# SDRAM_1.net
KiCad netlist of a schematic drawn in Altium Designer
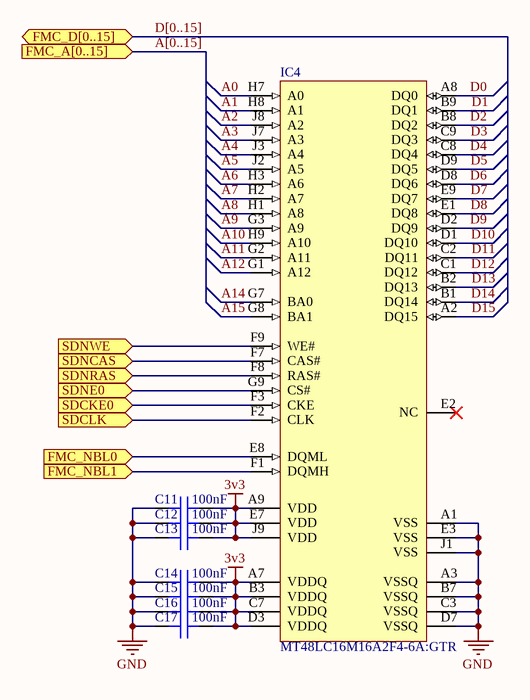
[diagram p0: SDRAM 1.SchDoc]

(export (version "E")
  (design (tool "Eeschema 10.0.6"))
  (components
    (comp (ref "C11")
      (value "100nF")
      (footprint "CAP 0603/1608")
      (description "Ceramic, SMT Capacitor")
      (fields
        (field (name "MANUFACTURER") "Samsung")
        (field (name "MANUFACTURER PART NUMBER") "CL10B104JB8NNNC")
      )
      (libsource (lib "yildizIoT Library") (part "Capacitor - Ceramic"))
    )
    (comp (ref "C12")
      (value "100nF")
      (footprint "CAP 0603/1608")
      (description "Ceramic, SMT Capacitor")
      (fields
        (field (name "MANUFACTURER") "Samsung")
        (field (name "MANUFACTURER PART NUMBER") "CL10B104JB8NNNC")
      )
      (libsource (lib "yildizIoT Library") (part "Capacitor - Ceramic"))
    )
    (comp (ref "C13")
      (value "100nF")
      (footprint "CAP 0603/1608")
      (description "Ceramic, SMT Capacitor")
      (fields
        (field (name "MANUFACTURER") "Samsung")
        (field (name "MANUFACTURER PART NUMBER") "CL10B104JB8NNNC")
      )
      (libsource (lib "yildizIoT Library") (part "Capacitor - Ceramic"))
    )
    (comp (ref "C14")
      (value "100nF")
      (footprint "CAP 0603/1608")
      (description "Ceramic, SMT Capacitor")
      (fields
        (field (name "MANUFACTURER") "Samsung")
        (field (name "MANUFACTURER PART NUMBER") "CL10B104JB8NNNC")
      )
      (libsource (lib "yildizIoT Library") (part "Capacitor - Ceramic"))
    )
    (comp (ref "C15")
      (value "100nF")
      (footprint "CAP 0603/1608")
      (description "Ceramic, SMT Capacitor")
      (fields
        (field (name "MANUFACTURER") "Samsung")
        (field (name "MANUFACTURER PART NUMBER") "CL10B104JB8NNNC")
      )
      (libsource (lib "yildizIoT Library") (part "Capacitor - Ceramic"))
    )
    (comp (ref "C16")
      (value "100nF")
      (footprint "CAP 0603/1608")
      (description "Ceramic, SMT Capacitor")
      (fields
        (field (name "MANUFACTURER") "Samsung")
        (field (name "MANUFACTURER PART NUMBER") "CL10B104JB8NNNC")
      )
      (libsource (lib "yildizIoT Library") (part "Capacitor - Ceramic"))
    )
    (comp (ref "C17")
      (value "100nF")
      (footprint "CAP 0603/1608")
      (description "Ceramic, SMT Capacitor")
      (fields
        (field (name "MANUFACTURER") "Samsung")
        (field (name "MANUFACTURER PART NUMBER") "CL10B104JB8NNNC")
      )
      (libsource (lib "yildizIoT Library") (part "Capacitor - Ceramic"))
    )
    (comp (ref "IC4")
      (value "MT48LC16M16A2F4-6A:GTR")
      (footprint "MICRON VFBGA-54 8X14MM")
      (fields (field (name "MANUFACTURER") "Alliance Memory"))
      (libsource (lib "yildizIoT Library") (part "MICRON 256Mb SDRAM"))
    )
  )
  (nets
    (net (code "2") (name "/A0") (class "Default")
      (node (ref "IC4") (pin "H7") (pinfunction "A0_H7") (pintype "input"))
    )
    (net (code "3") (name "/A1") (class "Default")
      (node (ref "IC4") (pin "H8") (pinfunction "A1_H8") (pintype "input"))
    )
    (net (code "4") (name "/A2") (class "Default")
      (node (ref "IC4") (pin "J8") (pinfunction "A2_J8") (pintype "input"))
    )
    (net (code "5") (name "/A3") (class "Default")
      (node (ref "IC4") (pin "J7") (pinfunction "A3_J7") (pintype "input"))
    )
    (net (code "6") (name "/A4") (class "Default")
      (node (ref "IC4") (pin "J3") (pinfunction "A4_J3") (pintype "input"))
    )
    (net (code "7") (name "/A5") (class "Default")
      (node (ref "IC4") (pin "J2") (pinfunction "A5_J2") (pintype "input"))
    )
    (net (code "8") (name "/A6") (class "Default")
      (node (ref "IC4") (pin "H3") (pinfunction "A6_H3") (pintype "input"))
    )
    (net (code "9") (name "/A7") (class "Default")
      (node (ref "IC4") (pin "H2") (pinfunction "A7_H2") (pintype "input"))
    )
    (net (code "10") (name "/A8") (class "Default")
      (node (ref "IC4") (pin "H1") (pinfunction "A8_H1") (pintype "input"))
    )
    (net (code "11") (name "/A9") (class "Default")
      (node (ref "IC4") (pin "G3") (pinfunction "A9_G3") (pintype "input"))
    )
    (net (code "12") (name "/A10") (class "Default")
      (node (ref "IC4") (pin "H9") (pinfunction "A10_H9") (pintype "input"))
    )
    (net (code "13") (name "/A11") (class "Default")
      (node (ref "IC4") (pin "G2") (pinfunction "A11_G2") (pintype "input"))
    )
    (net (code "14") (name "/A12") (class "Default")
      (node (ref "IC4") (pin "G1") (pinfunction "A12_G1") (pintype "input"))
    )
    (net (code "15") (name "/A14") (class "Default")
      (node (ref "IC4") (pin "G7") (pinfunction "BA0_G7") (pintype "input"))
    )
    (net (code "16") (name "/A15") (class "Default")
      (node (ref "IC4") (pin "G8") (pinfunction "BA1_G8") (pintype "input"))
    )
    (net (code "18") (name "/D0") (class "Default")
      (node (ref "IC4") (pin "A8") (pinfunction "DQ0_A8") (pintype "bidirectional"))
    )
    (net (code "19") (name "/D1") (class "Default")
      (node (ref "IC4") (pin "B9") (pinfunction "DQ1_B9") (pintype "bidirectional"))
    )
    (net (code "20") (name "/D2") (class "Default")
      (node (ref "IC4") (pin "B8") (pinfunction "DQ2_B8") (pintype "bidirectional"))
    )
    (net (code "21") (name "/D3") (class "Default")
      (node (ref "IC4") (pin "C9") (pinfunction "DQ3_C9") (pintype "bidirectional"))
    )
    (net (code "22") (name "/D4") (class "Default")
      (node (ref "IC4") (pin "C8") (pinfunction "DQ4_C8") (pintype "bidirectional"))
    )
    (net (code "23") (name "/D5") (class "Default")
      (node (ref "IC4") (pin "D9") (pinfunction "DQ5_D9") (pintype "bidirectional"))
    )
    (net (code "24") (name "/D6") (class "Default")
      (node (ref "IC4") (pin "D8") (pinfunction "DQ6_D8") (pintype "bidirectional"))
    )
    (net (code "25") (name "/D7") (class "Default")
      (node (ref "IC4") (pin "E9") (pinfunction "DQ7_E9") (pintype "bidirectional"))
    )
    (net (code "26") (name "/D8") (class "Default")
      (node (ref "IC4") (pin "E1") (pinfunction "DQ8_E1") (pintype "bidirectional"))
    )
    (net (code "27") (name "/D9") (class "Default")
      (node (ref "IC4") (pin "D2") (pinfunction "DQ9_D2") (pintype "bidirectional"))
    )
    (net (code "28") (name "/D10") (class "Default")
      (node (ref "IC4") (pin "D1") (pinfunction "DQ10_D1") (pintype "bidirectional"))
    )
    (net (code "29") (name "/D11") (class "Default")
      (node (ref "IC4") (pin "C2") (pinfunction "DQ11_C2") (pintype "bidirectional"))
    )
    (net (code "30") (name "/D12") (class "Default")
      (node (ref "IC4") (pin "C1") (pinfunction "DQ12_C1") (pintype "bidirectional"))
    )
    (net (code "31") (name "/D13") (class "Default")
      (node (ref "IC4") (pin "B2") (pinfunction "DQ13_B2") (pintype "bidirectional"))
    )
    (net (code "32") (name "/D14") (class "Default")
      (node (ref "IC4") (pin "B1") (pinfunction "DQ14_B1") (pintype "bidirectional"))
    )
    (net (code "33") (name "/D15") (class "Default")
      (node (ref "IC4") (pin "A2") (pinfunction "DQ15_A2") (pintype "bidirectional"))
    )
    (net (code "35") (name "/FMC_NBL0") (class "Default")
      (node (ref "IC4") (pin "E8") (pinfunction "DQML_E8") (pintype "input"))
    )
    (net (code "36") (name "/FMC_NBL1") (class "Default")
      (node (ref "IC4") (pin "F1") (pinfunction "DQMH_F1") (pintype "input"))
    )
    (net (code "37") (name "/SDCKE0") (class "Default")
      (node (ref "IC4") (pin "F3") (pinfunction "CKE_F3") (pintype "input"))
    )
    (net (code "38") (name "/SDCLK") (class "Default")
      (node (ref "IC4") (pin "F2") (pinfunction "CLK_F2") (pintype "input"))
    )
    (net (code "39") (name "/SDNCAS") (class "Default")
      (node (ref "IC4") (pin "F7") (pinfunction "CAS#_F7") (pintype "input"))
    )
    (net (code "40") (name "/SDNE0") (class "Default")
      (node (ref "IC4") (pin "G9") (pinfunction "CS#_G9") (pintype "input"))
    )
    (net (code "41") (name "/SDNRAS") (class "Default")
      (node (ref "IC4") (pin "F8") (pinfunction "RAS#_F8") (pintype "input"))
    )
    (net (code "42") (name "/SDNWE") (class "Default")
      (node (ref "IC4") (pin "F9") (pinfunction "WE#_F9") (pintype "input"))
    )
    (net (code "43") (name "3v3") (class "Default")
      (node (ref "C11") (pin "1") (pinfunction "1_1") (pintype "passive"))
      (node (ref "C12") (pin "1") (pinfunction "1_1") (pintype "passive"))
      (node (ref "C13") (pin "1") (pinfunction "1_1") (pintype "passive"))
      (node (ref "C14") (pin "1") (pinfunction "1_1") (pintype "passive"))
      (node (ref "C15") (pin "1") (pinfunction "1_1") (pintype "passive"))
      (node (ref "C16") (pin "1") (pinfunction "1_1") (pintype "passive"))
      (node (ref "C17") (pin "1") (pinfunction "1_1") (pintype "passive"))
      (node (ref "IC4") (pin "A7") (pinfunction "VDDQ_A7") (pintype "power_in"))
      (node (ref "IC4") (pin "A9") (pinfunction "VDD_A9") (pintype "power_in"))
      (node (ref "IC4") (pin "B3") (pinfunction "VDDQ_B3") (pintype "power_in"))
      (node (ref "IC4") (pin "C7") (pinfunction "VDDQ_C7") (pintype "power_in"))
      (node (ref "IC4") (pin "D3") (pinfunction "VDDQ_D3") (pintype "power_in"))
      (node (ref "IC4") (pin "E7") (pinfunction "VDD_E7") (pintype "power_in"))
      (node (ref "IC4") (pin "J9") (pinfunction "VDD_J9") (pintype "power_in"))
    )
    (net (code "44") (name "GND") (class "Default")
      (node (ref "C11") (pin "2") (pinfunction "2_2") (pintype "passive"))
      (node (ref "C12") (pin "2") (pinfunction "2_2") (pintype "passive"))
      (node (ref "C13") (pin "2") (pinfunction "2_2") (pintype "passive"))
      (node (ref "C14") (pin "2") (pinfunction "2_2") (pintype "passive"))
      (node (ref "C15") (pin "2") (pinfunction "2_2") (pintype "passive"))
      (node (ref "C16") (pin "2") (pinfunction "2_2") (pintype "passive"))
      (node (ref "C17") (pin "2") (pinfunction "2_2") (pintype "passive"))
      (node (ref "IC4") (pin "A1") (pinfunction "VSS_A1") (pintype "power_in"))
      (node (ref "IC4") (pin "A3") (pinfunction "VSSQ_A3") (pintype "power_in"))
      (node (ref "IC4") (pin "B7") (pinfunction "VSSQ_B7") (pintype "power_in"))
      (node (ref "IC4") (pin "C3") (pinfunction "VSSQ_C3") (pintype "power_in"))
      (node (ref "IC4") (pin "D7") (pinfunction "VSSQ_D7") (pintype "power_in"))
      (node (ref "IC4") (pin "E3") (pinfunction "VSS_E3") (pintype "power_in"))
      (node (ref "IC4") (pin "J1") (pinfunction "VSS_J1") (pintype "power_in"))
    )
    (net (code "45") (name "unconnected-(IC4-NC-PadE2)") (class "Default")
      (node (ref "IC4") (pin "E2") (pinfunction "NC_E2") (pintype "passive+no_connect"))
    )
  )
)
